# Buck_Regulator.net
KiCad netlist of a schematic drawn in EAGLE
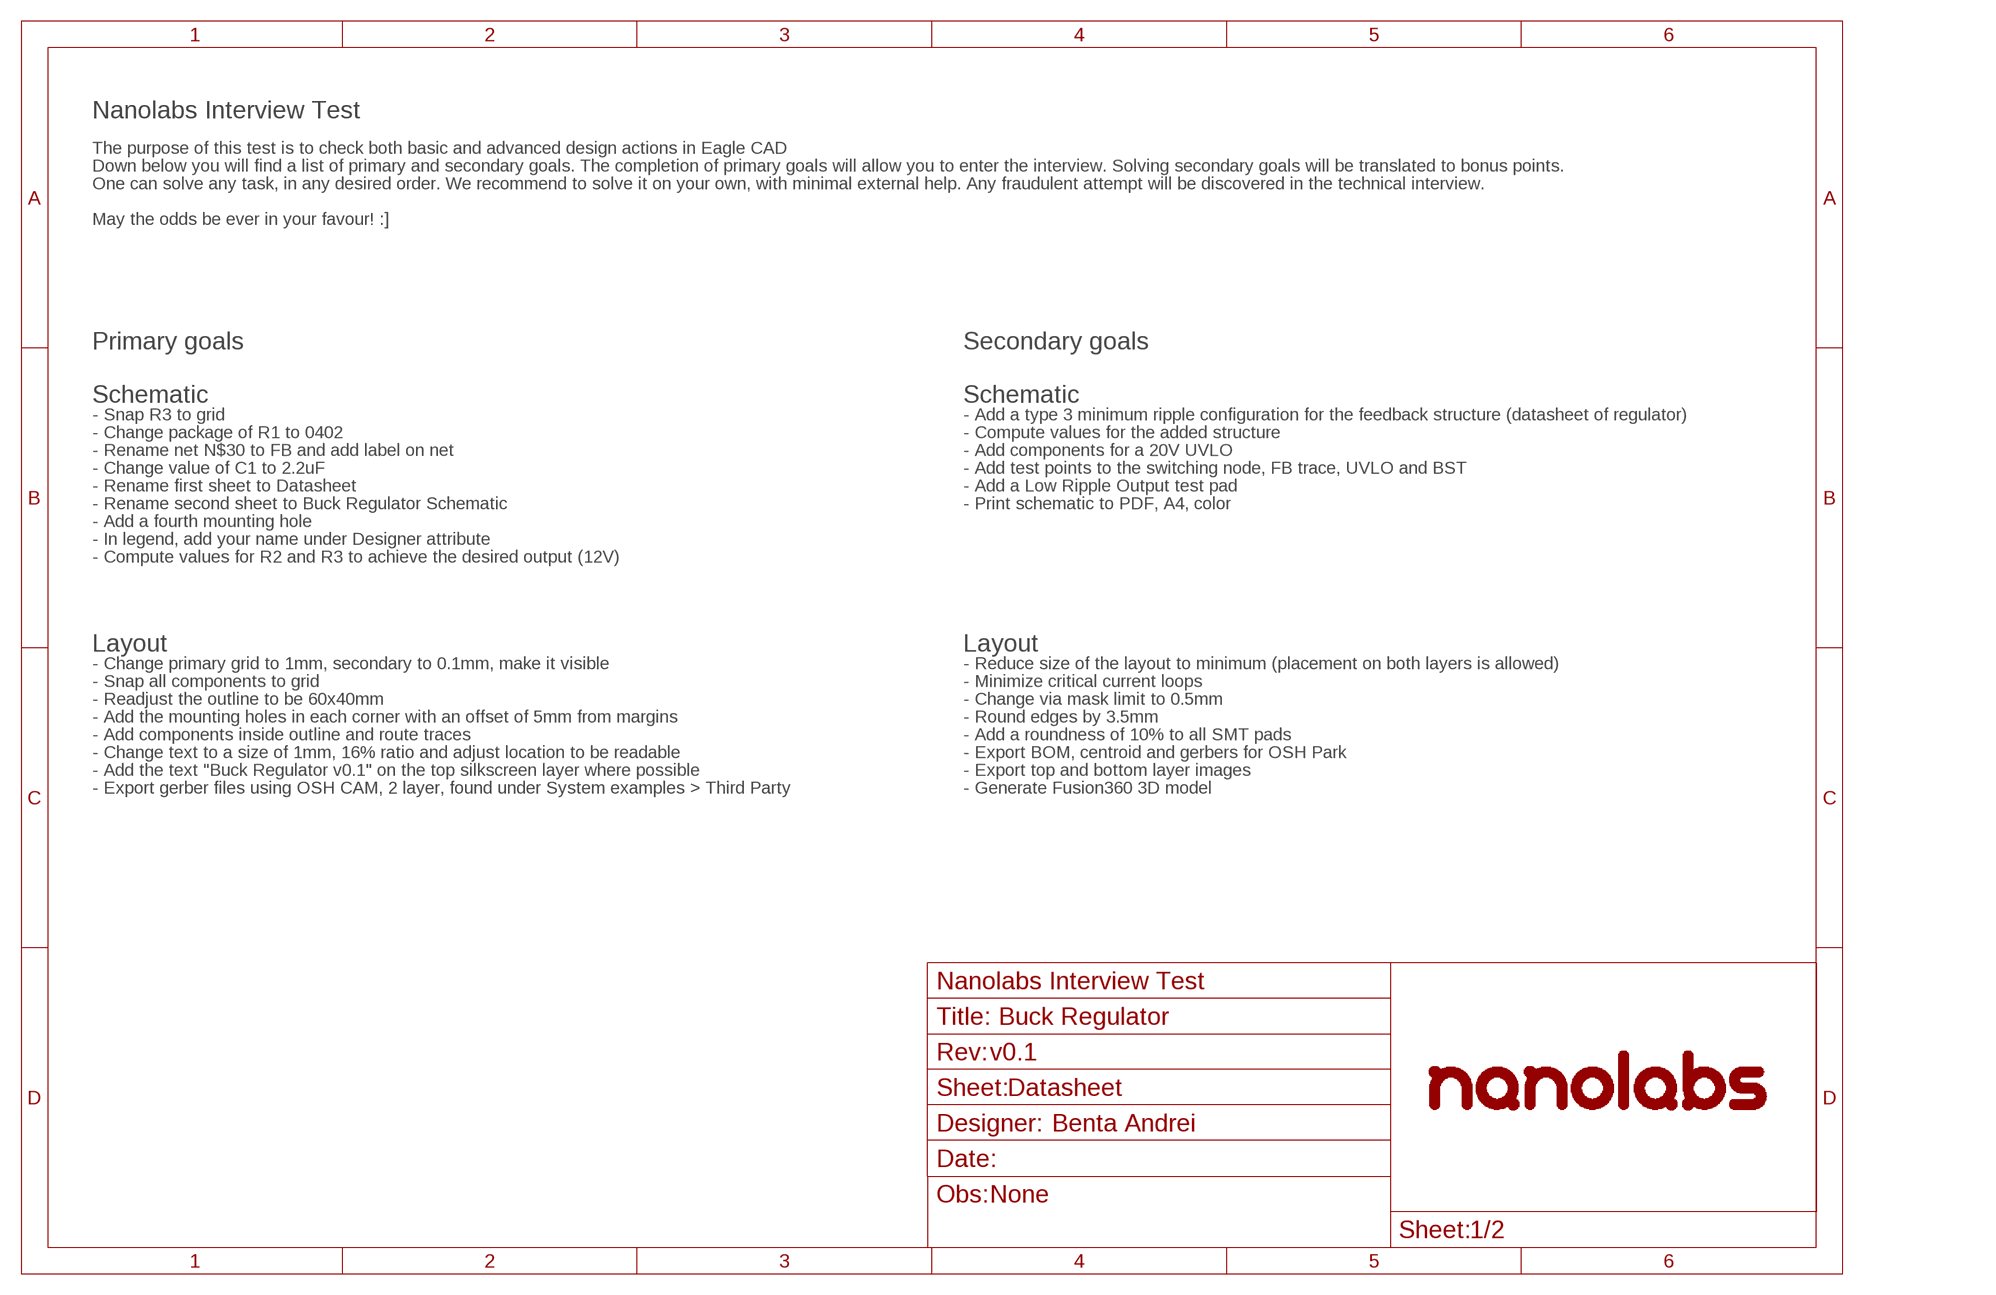
[diagram p0: schematic, sheet 1]
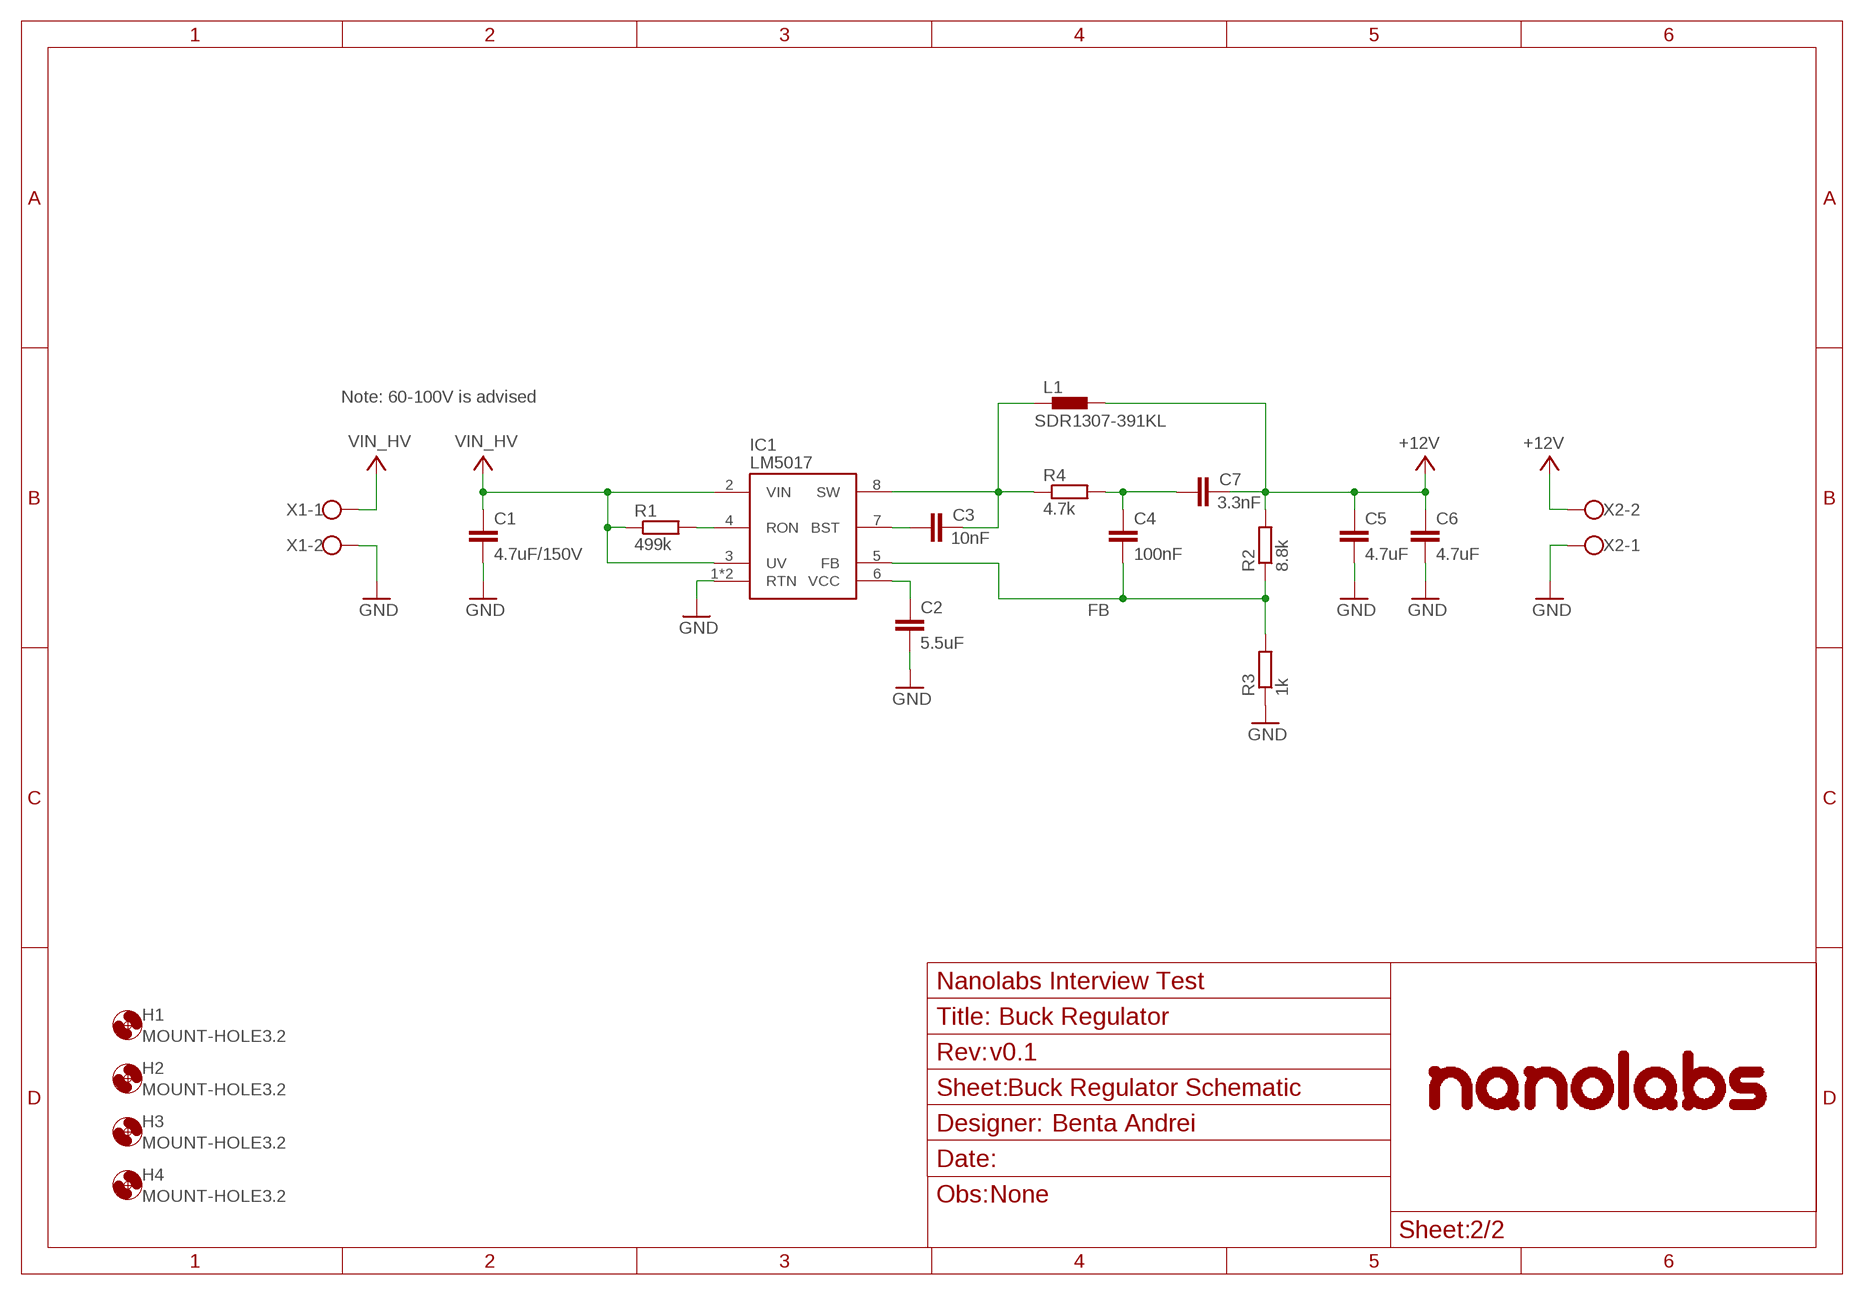
[diagram p1: schematic, sheet 2]

(export (version "E")
  (design (tool "Eeschema 10.0.6"))
  (components
    (comp (ref "C1")
      (value "4.7uF/150V")
      (footprint "eagle-import:C1812")
      (libsource (lib "eagle-import") (part "C-EUC1812"))
    )
    (comp (ref "C2")
      (value "5.5uF")
      (footprint "eagle-import:C0603")
      (libsource (lib "eagle-import") (part "C-EUC0603"))
    )
    (comp (ref "C3")
      (value "10nF")
      (footprint "eagle-import:C0603")
      (libsource (lib "eagle-import") (part "C-EUC0603"))
    )
    (comp (ref "C4")
      (value "100nF")
      (footprint "eagle-import:C0603")
      (libsource (lib "eagle-import") (part "C-EUC0603"))
    )
    (comp (ref "C5")
      (value "4.7uF")
      (footprint "eagle-import:C0603")
      (libsource (lib "eagle-import") (part "C-EUC0603"))
    )
    (comp (ref "C6")
      (value "4.7uF")
      (footprint "eagle-import:C0603")
      (libsource (lib "eagle-import") (part "C-EUC0603"))
    )
    (comp (ref "C7")
      (value "3.3nF")
      (footprint "eagle-import:C0603")
      (libsource (lib "eagle-import") (part "C-EUC0603"))
    )
    (comp (ref "H1")
      (value "MOUNT-HOLE3.2")
      (footprint "eagle-import:3,2")
      (libsource (lib "eagle-import") (part "MOUNT-HOLE3.2"))
    )
    (comp (ref "H2")
      (value "MOUNT-HOLE3.2")
      (footprint "eagle-import:3,2")
      (libsource (lib "eagle-import") (part "MOUNT-HOLE3.2"))
    )
    (comp (ref "H3")
      (value "MOUNT-HOLE3.2")
      (footprint "eagle-import:3,2")
      (libsource (lib "eagle-import") (part "MOUNT-HOLE3.2"))
    )
    (comp (ref "H4")
      (value "MOUNT-HOLE3.2")
      (footprint "eagle-import:3,2")
      (libsource (lib "eagle-import") (part "MOUNT-HOLE3.2"))
    )
    (comp (ref "IC1")
      (value "LM5017")
      (footprint "eagle-import:SO-08-EP")
      (libsource (lib "eagle-import") (part "LM5017"))
    )
    (comp (ref "L1")
      (value "SDR1307-391KL")
      (footprint "eagle-import:SDR1307-391KL")
      (libsource (lib "eagle-import") (part "SDR1307-391KL"))
    )
    (comp (ref "R1")
      (value "499k")
      (footprint "eagle-import:R0603")
      (libsource (lib "eagle-import") (part "R-EU_R0603"))
    )
    (comp (ref "R2")
      (value "8.8k")
      (footprint "eagle-import:R0603")
      (libsource (lib "eagle-import") (part "R-EU_R0603"))
    )
    (comp (ref "R3")
      (value "1k")
      (footprint "eagle-import:R0603")
      (libsource (lib "eagle-import") (part "R-EU_R0603"))
    )
    (comp (ref "R4")
      (value "4.7k")
      (footprint "eagle-import:R0603")
      (libsource (lib "eagle-import") (part "R-EU_R0603"))
    )
    (comp (ref "X1")
      (value "W237-102")
      (footprint "eagle-import:W237-102")
      (fields (field (name "MPN") "237-102"))
      (libsource (lib "eagle-import") (part "W237-102"))
    )
    (comp (ref "X2")
      (value "W237-102")
      (footprint "eagle-import:W237-102")
      (fields (field (name "MPN") "237-102"))
      (libsource (lib "eagle-import") (part "W237-102"))
    )
  )
  (nets
    (net (code "1") (name "+12V") (class "Default")
      (node (ref "C5") (pin "1") (pinfunction "1_1") (pintype "passive"))
      (node (ref "C6") (pin "1") (pinfunction "1_1") (pintype "passive"))
      (node (ref "C7") (pin "2") (pinfunction "2_2") (pintype "passive"))
      (node (ref "L1") (pin "2") (pinfunction "2_2") (pintype "passive"))
      (node (ref "R2") (pin "2") (pinfunction "2_2") (pintype "passive"))
      (node (ref "X2") (pin "2") (pinfunction "KL_2") (pintype "passive"))
    )
    (net (code "2") (name "FB") (class "Default")
      (node (ref "C4") (pin "2") (pinfunction "2_2") (pintype "passive"))
      (node (ref "IC1") (pin "5") (pinfunction "FB_5") (pintype "bidirectional"))
      (node (ref "R2") (pin "1") (pinfunction "1_1") (pintype "passive"))
      (node (ref "R3") (pin "2") (pinfunction "2_2") (pintype "passive"))
    )
    (net (code "3") (name "GND") (class "Default")
      (node (ref "C1") (pin "2") (pinfunction "2_2") (pintype "passive"))
      (node (ref "C2") (pin "2") (pinfunction "2_2") (pintype "passive"))
      (node (ref "C5") (pin "2") (pinfunction "2_2") (pintype "passive"))
      (node (ref "C6") (pin "2") (pinfunction "2_2") (pintype "passive"))
      (node (ref "IC1") (pin "1") (pinfunction "RTN_1") (pintype "bidirectional"))
      (node (ref "IC1") (pin "9") (pinfunction "RTN_9") (pintype "bidirectional"))
      (node (ref "R3") (pin "1") (pinfunction "1_1") (pintype "passive"))
      (node (ref "X1") (pin "2") (pinfunction "KL_2") (pintype "passive"))
      (node (ref "X2") (pin "1") (pinfunction "KL_1") (pintype "passive"))
    )
    (net (code "4") (name "Net-(C4-Pad1)") (class "Default")
      (node (ref "C4") (pin "1") (pinfunction "1_1") (pintype "passive"))
      (node (ref "C7") (pin "1") (pinfunction "1_1") (pintype "passive"))
      (node (ref "R4") (pin "2") (pinfunction "2_2") (pintype "passive"))
    )
    (net (code "5") (name "Net-(IC1-BST)") (class "Default")
      (node (ref "C3") (pin "1") (pinfunction "1_1") (pintype "passive"))
      (node (ref "IC1") (pin "7") (pinfunction "BST_7") (pintype "bidirectional"))
    )
    (net (code "6") (name "Net-(IC1-RON)") (class "Default")
      (node (ref "IC1") (pin "4") (pinfunction "RON_4") (pintype "bidirectional"))
      (node (ref "R1") (pin "2") (pinfunction "2_2") (pintype "passive"))
    )
    (net (code "7") (name "Net-(IC1-SW)") (class "Default")
      (node (ref "C3") (pin "2") (pinfunction "2_2") (pintype "passive"))
      (node (ref "IC1") (pin "8") (pinfunction "SW_8") (pintype "bidirectional"))
      (node (ref "L1") (pin "1") (pinfunction "1_1") (pintype "passive"))
      (node (ref "R4") (pin "1") (pinfunction "1_1") (pintype "passive"))
    )
    (net (code "8") (name "Net-(IC1-VCC)") (class "Default")
      (node (ref "C2") (pin "1") (pinfunction "1_1") (pintype "passive"))
      (node (ref "IC1") (pin "6") (pinfunction "VCC_6") (pintype "bidirectional"))
    )
    (net (code "9") (name "VIN_HV") (class "Default")
      (node (ref "C1") (pin "1") (pinfunction "1_1") (pintype "passive"))
      (node (ref "IC1") (pin "2") (pinfunction "VIN_2") (pintype "bidirectional"))
      (node (ref "IC1") (pin "3") (pinfunction "UV_3") (pintype "bidirectional"))
      (node (ref "R1") (pin "1") (pinfunction "1_1") (pintype "passive"))
      (node (ref "X1") (pin "1") (pinfunction "KL_1") (pintype "passive"))
    )
  )
)
